# Sheet1.net
KiCad netlist of a schematic drawn in Altium Designer
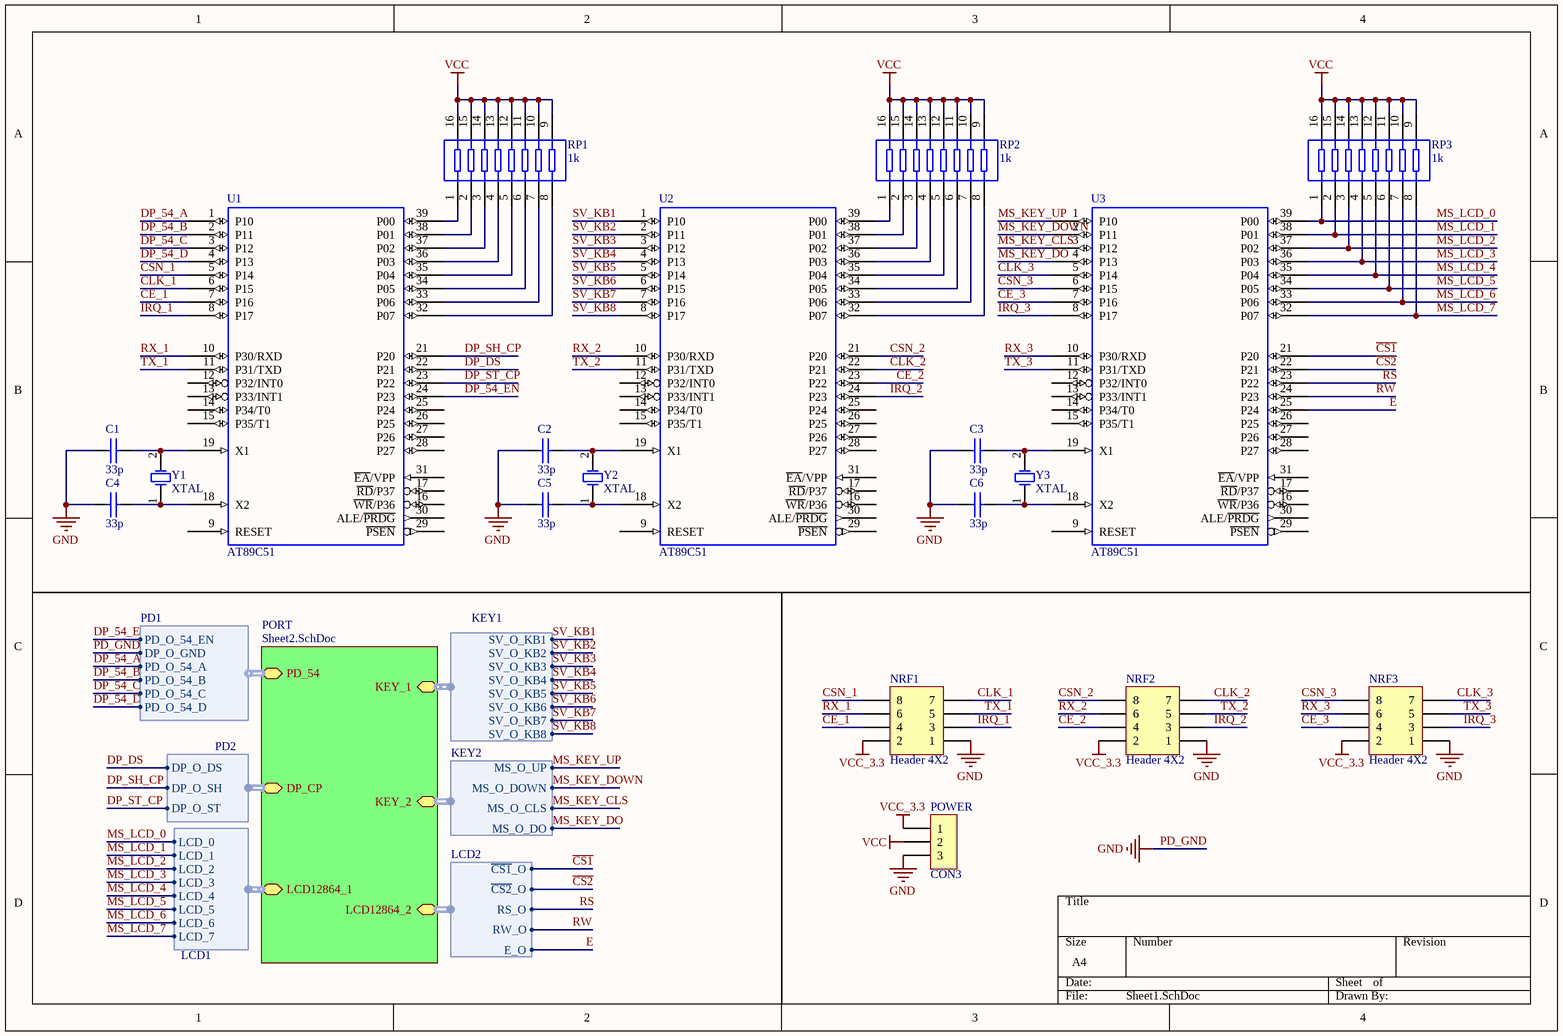
[diagram p0: Sheet1.SchDoc]

(export (version "E")
  (design (tool "Eeschema 10.0.6"))
  (components
    (comp (ref "C1")
      (value "33p")
      (footprint "RAD0.1")
      (description "Capacitor")
      (libsource (lib "电容") (part "普通电容"))
    )
    (comp (ref "C2")
      (value "33p")
      (footprint "RAD0.1")
      (description "Capacitor")
      (libsource (lib "电容") (part "普通电容"))
    )
    (comp (ref "C3")
      (value "33p")
      (footprint "RAD0.1")
      (description "Capacitor")
      (libsource (lib "电容") (part "普通电容"))
    )
    (comp (ref "C4")
      (value "33p")
      (footprint "RAD0.1")
      (description "Capacitor")
      (libsource (lib "电容") (part "普通电容"))
    )
    (comp (ref "C5")
      (value "33p")
      (footprint "RAD0.1")
      (description "Capacitor")
      (libsource (lib "电容") (part "普通电容"))
    )
    (comp (ref "C6")
      (value "33p")
      (footprint "RAD0.1")
      (description "Capacitor")
      (libsource (lib "电容") (part "普通电容"))
    )
    (comp (ref "NRF1")
      (value "Header 4X2")
      (footprint "HDR2X4")
      (description "Header, 4-Pin, Dual row")
      (fields (field (name "PUBLISHER") "Altium Limited"))
      (libsource (lib "Miscellaneous Connectors") (part "Header 4X2"))
    )
    (comp (ref "NRF2")
      (value "Header 4X2")
      (footprint "HDR2X4")
      (description "Header, 4-Pin, Dual row")
      (fields (field (name "PUBLISHER") "Altium Limited"))
      (libsource (lib "Miscellaneous Connectors") (part "Header 4X2"))
    )
    (comp (ref "NRF3")
      (value "Header 4X2")
      (footprint "HDR2X4")
      (description "Header, 4-Pin, Dual row")
      (fields (field (name "PUBLISHER") "Altium Limited"))
      (libsource (lib "Miscellaneous Connectors") (part "Header 4X2"))
    )
    (comp (ref "POWER") (value "CON3") (description "Connector") (libsource (lib "插件") (part "CON3")))
    (comp (ref "RP1") (value "1k") (footprint "DIP16") (libsource (lib "电阻") (part "RESPACK4")))
    (comp (ref "RP2") (value "1k") (footprint "DIP16") (libsource (lib "电阻") (part "RESPACK4")))
    (comp (ref "RP3") (value "1k") (footprint "DIP16") (libsource (lib "电阻") (part "RESPACK4")))
    (comp (ref "U1") (value "AT89C51") (footprint "DIP-40") (libsource (lib "单片机及相关") (part "AT89C51")))
    (comp (ref "U2") (value "AT89C51") (footprint "DIP-40") (libsource (lib "单片机及相关") (part "AT89C51")))
    (comp (ref "U3") (value "AT89C51") (footprint "DIP-40") (libsource (lib "单片机及相关") (part "AT89C51")))
    (comp (ref "Y1") (value "XTAL") (footprint "XTAL") (libsource (lib "我的元件库") (part "XTAL")))
    (comp (ref "Y2") (value "XTAL") (footprint "XTAL") (libsource (lib "我的元件库") (part "XTAL")))
    (comp (ref "Y3") (value "XTAL") (footprint "XTAL") (libsource (lib "我的元件库") (part "XTAL")))
  )
  (nets
    (net (code "7") (name "/CE_1") (class "Default")
      (node (ref "NRF1") (pin "4") (pinfunction "4_4") (pintype "passive"))
      (node (ref "U1") (pin "7") (pinfunction "P16_7") (pintype "bidirectional"))
    )
    (net (code "8") (name "/CE_2") (class "Default")
      (node (ref "NRF2") (pin "4") (pinfunction "4_4") (pintype "passive"))
      (node (ref "U2") (pin "23") (pinfunction "P22_23") (pintype "bidirectional"))
    )
    (net (code "9") (name "/CE_3") (class "Default")
      (node (ref "NRF3") (pin "4") (pinfunction "4_4") (pintype "passive"))
      (node (ref "U3") (pin "7") (pinfunction "P16_7") (pintype "bidirectional"))
    )
    (net (code "10") (name "/CLK_1") (class "Default")
      (node (ref "NRF1") (pin "7") (pinfunction "7_7") (pintype "passive"))
      (node (ref "U1") (pin "6") (pinfunction "P15_6") (pintype "bidirectional"))
    )
    (net (code "11") (name "/CLK_2") (class "Default")
      (node (ref "NRF2") (pin "7") (pinfunction "7_7") (pintype "passive"))
      (node (ref "U2") (pin "22") (pinfunction "P21_22") (pintype "bidirectional"))
    )
    (net (code "12") (name "/CLK_3") (class "Default")
      (node (ref "NRF3") (pin "7") (pinfunction "7_7") (pintype "passive"))
      (node (ref "U3") (pin "5") (pinfunction "P14_5") (pintype "bidirectional"))
    )
    (net (code "13") (name "/CSN_1") (class "Default")
      (node (ref "NRF1") (pin "8") (pinfunction "8_8") (pintype "passive"))
      (node (ref "U1") (pin "5") (pinfunction "P14_5") (pintype "bidirectional"))
    )
    (net (code "14") (name "/CSN_2") (class "Default")
      (node (ref "NRF2") (pin "8") (pinfunction "8_8") (pintype "passive"))
      (node (ref "U2") (pin "21") (pinfunction "P20_21") (pintype "bidirectional"))
    )
    (net (code "15") (name "/CSN_3") (class "Default")
      (node (ref "NRF3") (pin "8") (pinfunction "8_8") (pintype "passive"))
      (node (ref "U3") (pin "6") (pinfunction "P15_6") (pintype "bidirectional"))
    )
    (net (code "16") (name "/DP_54_A") (class "Default")
      (node (ref "U1") (pin "1") (pinfunction "P10_1") (pintype "bidirectional"))
    )
    (net (code "17") (name "/DP_54_B") (class "Default")
      (node (ref "U1") (pin "2") (pinfunction "P11_2") (pintype "bidirectional"))
    )
    (net (code "18") (name "/DP_54_C") (class "Default")
      (node (ref "U1") (pin "3") (pinfunction "P12_3") (pintype "bidirectional"))
    )
    (net (code "19") (name "/DP_54_D") (class "Default")
      (node (ref "U1") (pin "4") (pinfunction "P13_4") (pintype "bidirectional"))
    )
    (net (code "20") (name "/DP_54_EN") (class "Default")
      (node (ref "U1") (pin "24") (pinfunction "P23_24") (pintype "bidirectional"))
    )
    (net (code "21") (name "/DP_DS") (class "Default")
      (node (ref "U1") (pin "22") (pinfunction "P21_22") (pintype "bidirectional"))
    )
    (net (code "22") (name "/DP_SH_CP") (class "Default")
      (node (ref "U1") (pin "21") (pinfunction "P20_21") (pintype "bidirectional"))
    )
    (net (code "23") (name "/DP_ST_CP") (class "Default")
      (node (ref "U1") (pin "23") (pinfunction "P22_23") (pintype "bidirectional"))
    )
    (net (code "24") (name "/E") (class "Default")
      (node (ref "U3") (pin "25") (pinfunction "P24_25") (pintype "bidirectional"))
    )
    (net (code "25") (name "/IRQ_1") (class "Default")
      (node (ref "NRF1") (pin "3") (pinfunction "3_3") (pintype "passive"))
      (node (ref "U1") (pin "8") (pinfunction "P17_8") (pintype "bidirectional"))
    )
    (net (code "26") (name "/IRQ_2") (class "Default")
      (node (ref "NRF2") (pin "3") (pinfunction "3_3") (pintype "passive"))
      (node (ref "U2") (pin "24") (pinfunction "P23_24") (pintype "bidirectional"))
    )
    (net (code "27") (name "/IRQ_3") (class "Default")
      (node (ref "NRF3") (pin "3") (pinfunction "3_3") (pintype "passive"))
      (node (ref "U3") (pin "8") (pinfunction "P17_8") (pintype "bidirectional"))
    )
    (net (code "28") (name "/MS_KEY_CLS") (class "Default")
      (node (ref "U3") (pin "3") (pinfunction "P12_3") (pintype "bidirectional"))
    )
    (net (code "29") (name "/MS_KEY_DO") (class "Default")
      (node (ref "U3") (pin "4") (pinfunction "P13_4") (pintype "bidirectional"))
    )
    (net (code "30") (name "/MS_KEY_DOWN") (class "Default")
      (node (ref "U3") (pin "2") (pinfunction "P11_2") (pintype "bidirectional"))
    )
    (net (code "31") (name "/MS_KEY_UP") (class "Default")
      (node (ref "U3") (pin "1") (pinfunction "P10_1") (pintype "bidirectional"))
    )
    (net (code "32") (name "/MS_LCD_0") (class "Default")
      (node (ref "RP3") (pin "1") (pinfunction "1_1") (pintype "passive"))
      (node (ref "U3") (pin "39") (pinfunction "P00_39") (pintype "bidirectional"))
    )
    (net (code "33") (name "/MS_LCD_1") (class "Default")
      (node (ref "RP3") (pin "2") (pinfunction "2_2") (pintype "passive"))
      (node (ref "U3") (pin "38") (pinfunction "P01_38") (pintype "bidirectional"))
    )
    (net (code "34") (name "/MS_LCD_2") (class "Default")
      (node (ref "RP3") (pin "3") (pinfunction "3_3") (pintype "passive"))
      (node (ref "U3") (pin "37") (pinfunction "P02_37") (pintype "bidirectional"))
    )
    (net (code "35") (name "/MS_LCD_3") (class "Default")
      (node (ref "RP3") (pin "4") (pinfunction "4_4") (pintype "passive"))
      (node (ref "U3") (pin "36") (pinfunction "P03_36") (pintype "bidirectional"))
    )
    (net (code "36") (name "/MS_LCD_4") (class "Default")
      (node (ref "RP3") (pin "5") (pinfunction "5_5") (pintype "passive"))
      (node (ref "U3") (pin "35") (pinfunction "P04_35") (pintype "bidirectional"))
    )
    (net (code "37") (name "/MS_LCD_5") (class "Default")
      (node (ref "RP3") (pin "6") (pinfunction "6_6") (pintype "passive"))
      (node (ref "U3") (pin "34") (pinfunction "P05_34") (pintype "bidirectional"))
    )
    (net (code "38") (name "/MS_LCD_6") (class "Default")
      (node (ref "RP3") (pin "7") (pinfunction "7_7") (pintype "passive"))
      (node (ref "U3") (pin "33") (pinfunction "P06_33") (pintype "bidirectional"))
    )
    (net (code "39") (name "/MS_LCD_7") (class "Default")
      (node (ref "RP3") (pin "8") (pinfunction "8_8") (pintype "passive"))
      (node (ref "U3") (pin "32") (pinfunction "P07_32") (pintype "bidirectional"))
    )
    (net (code "40") (name "/RS") (class "Default")
      (node (ref "U3") (pin "23") (pinfunction "P22_23") (pintype "bidirectional"))
    )
    (net (code "41") (name "/RW") (class "Default")
      (node (ref "U3") (pin "24") (pinfunction "P23_24") (pintype "bidirectional"))
    )
    (net (code "42") (name "/RX_1") (class "Default")
      (node (ref "NRF1") (pin "6") (pinfunction "6_6") (pintype "passive"))
      (node (ref "U1") (pin "10") (pinfunction "P30/RXD_10") (pintype "bidirectional"))
    )
    (net (code "43") (name "/RX_2") (class "Default")
      (node (ref "NRF2") (pin "6") (pinfunction "6_6") (pintype "passive"))
      (node (ref "U2") (pin "10") (pinfunction "P30/RXD_10") (pintype "bidirectional"))
    )
    (net (code "44") (name "/RX_3") (class "Default")
      (node (ref "NRF3") (pin "6") (pinfunction "6_6") (pintype "passive"))
      (node (ref "U3") (pin "10") (pinfunction "P30/RXD_10") (pintype "bidirectional"))
    )
    (net (code "45") (name "/SV_KB1") (class "Default")
      (node (ref "U2") (pin "1") (pinfunction "P10_1") (pintype "bidirectional"))
    )
    (net (code "46") (name "/SV_KB2") (class "Default")
      (node (ref "U2") (pin "2") (pinfunction "P11_2") (pintype "bidirectional"))
    )
    (net (code "47") (name "/SV_KB3") (class "Default")
      (node (ref "U2") (pin "3") (pinfunction "P12_3") (pintype "bidirectional"))
    )
    (net (code "48") (name "/SV_KB4") (class "Default")
      (node (ref "U2") (pin "4") (pinfunction "P13_4") (pintype "bidirectional"))
    )
    (net (code "49") (name "/SV_KB5") (class "Default")
      (node (ref "U2") (pin "5") (pinfunction "P14_5") (pintype "bidirectional"))
    )
    (net (code "50") (name "/SV_KB6") (class "Default")
      (node (ref "U2") (pin "6") (pinfunction "P15_6") (pintype "bidirectional"))
    )
    (net (code "51") (name "/SV_KB7") (class "Default")
      (node (ref "U2") (pin "7") (pinfunction "P16_7") (pintype "bidirectional"))
    )
    (net (code "52") (name "/SV_KB8") (class "Default")
      (node (ref "U2") (pin "8") (pinfunction "P17_8") (pintype "bidirectional"))
    )
    (net (code "53") (name "/TX_1") (class "Default")
      (node (ref "NRF1") (pin "5") (pinfunction "5_5") (pintype "passive"))
      (node (ref "U1") (pin "11") (pinfunction "P31/TXD_11") (pintype "bidirectional"))
    )
    (net (code "54") (name "/TX_2") (class "Default")
      (node (ref "NRF2") (pin "5") (pinfunction "5_5") (pintype "passive"))
      (node (ref "U2") (pin "11") (pinfunction "P31/TXD_11") (pintype "bidirectional"))
    )
    (net (code "55") (name "/TX_3") (class "Default")
      (node (ref "NRF3") (pin "5") (pinfunction "5_5") (pintype "passive"))
      (node (ref "U3") (pin "11") (pinfunction "P31/TXD_11") (pintype "bidirectional"))
    )
    (net (code "62") (name "/~{CS1}") (class "Default")
      (node (ref "U3") (pin "21") (pinfunction "P20_21") (pintype "bidirectional"))
    )
    (net (code "63") (name "/~{CS2}") (class "Default")
      (node (ref "U3") (pin "22") (pinfunction "P21_22") (pintype "bidirectional"))
    )
    (net (code "64") (name "GND") (class "Default")
      (node (ref "C1") (pin "1") (pinfunction "1_1") (pintype "passive"))
      (node (ref "C2") (pin "1") (pinfunction "1_1") (pintype "passive"))
      (node (ref "C3") (pin "1") (pinfunction "1_1") (pintype "passive"))
      (node (ref "C4") (pin "1") (pinfunction "1_1") (pintype "passive"))
      (node (ref "C5") (pin "1") (pinfunction "1_1") (pintype "passive"))
      (node (ref "C6") (pin "1") (pinfunction "1_1") (pintype "passive"))
      (node (ref "NRF1") (pin "1") (pinfunction "1_1") (pintype "passive"))
      (node (ref "NRF2") (pin "1") (pinfunction "1_1") (pintype "passive"))
      (node (ref "NRF3") (pin "1") (pinfunction "1_1") (pintype "passive"))
      (node (ref "POWER") (pin "3") (pinfunction "3_3") (pintype "passive"))
      (node (ref "U1") (pin "20") (pinfunction "GND_20") (pintype "power_in"))
      (node (ref "U2") (pin "20") (pinfunction "GND_20") (pintype "power_in"))
      (node (ref "U3") (pin "20") (pinfunction "GND_20") (pintype "power_in"))
    )
    (net (code "65") (name "Net-(U1-P00)") (class "Default")
      (node (ref "RP1") (pin "1") (pinfunction "1_1") (pintype "passive"))
      (node (ref "U1") (pin "39") (pinfunction "P00_39") (pintype "bidirectional"))
    )
    (net (code "66") (name "Net-(U1-P01)") (class "Default")
      (node (ref "RP1") (pin "2") (pinfunction "2_2") (pintype "passive"))
      (node (ref "U1") (pin "38") (pinfunction "P01_38") (pintype "bidirectional"))
    )
    (net (code "67") (name "Net-(U1-P02)") (class "Default")
      (node (ref "RP1") (pin "3") (pinfunction "3_3") (pintype "passive"))
      (node (ref "U1") (pin "37") (pinfunction "P02_37") (pintype "bidirectional"))
    )
    (net (code "68") (name "Net-(U1-P03)") (class "Default")
      (node (ref "RP1") (pin "4") (pinfunction "4_4") (pintype "passive"))
      (node (ref "U1") (pin "36") (pinfunction "P03_36") (pintype "bidirectional"))
    )
    (net (code "69") (name "Net-(U1-P04)") (class "Default")
      (node (ref "RP1") (pin "5") (pinfunction "5_5") (pintype "passive"))
      (node (ref "U1") (pin "35") (pinfunction "P04_35") (pintype "bidirectional"))
    )
    (net (code "70") (name "Net-(U1-P05)") (class "Default")
      (node (ref "RP1") (pin "6") (pinfunction "6_6") (pintype "passive"))
      (node (ref "U1") (pin "34") (pinfunction "P05_34") (pintype "bidirectional"))
    )
    (net (code "71") (name "Net-(U1-P06)") (class "Default")
      (node (ref "RP1") (pin "7") (pinfunction "7_7") (pintype "passive"))
      (node (ref "U1") (pin "33") (pinfunction "P06_33") (pintype "bidirectional"))
    )
    (net (code "72") (name "Net-(U1-P07)") (class "Default")
      (node (ref "RP1") (pin "8") (pinfunction "8_8") (pintype "passive"))
      (node (ref "U1") (pin "32") (pinfunction "P07_32") (pintype "bidirectional"))
    )
    (net (code "73") (name "Net-(U1-X1)") (class "Default")
      (node (ref "C1") (pin "2") (pinfunction "2_2") (pintype "passive"))
      (node (ref "U1") (pin "19") (pinfunction "X1_19") (pintype "input"))
      (node (ref "Y1") (pin "2") (pinfunction "2_2") (pintype "passive"))
    )
    (net (code "74") (name "Net-(U1-X2)") (class "Default")
      (node (ref "C4") (pin "2") (pinfunction "2_2") (pintype "passive"))
      (node (ref "U1") (pin "18") (pinfunction "X2_18") (pintype "input"))
      (node (ref "Y1") (pin "1") (pinfunction "1_1") (pintype "passive"))
    )
    (net (code "75") (name "Net-(U2-P00)") (class "Default")
      (node (ref "RP2") (pin "1") (pinfunction "1_1") (pintype "passive"))
      (node (ref "U2") (pin "39") (pinfunction "P00_39") (pintype "bidirectional"))
    )
    (net (code "76") (name "Net-(U2-P01)") (class "Default")
      (node (ref "RP2") (pin "2") (pinfunction "2_2") (pintype "passive"))
      (node (ref "U2") (pin "38") (pinfunction "P01_38") (pintype "bidirectional"))
    )
    (net (code "77") (name "Net-(U2-P02)") (class "Default")
      (node (ref "RP2") (pin "3") (pinfunction "3_3") (pintype "passive"))
      (node (ref "U2") (pin "37") (pinfunction "P02_37") (pintype "bidirectional"))
    )
    (net (code "78") (name "Net-(U2-P03)") (class "Default")
      (node (ref "RP2") (pin "4") (pinfunction "4_4") (pintype "passive"))
      (node (ref "U2") (pin "36") (pinfunction "P03_36") (pintype "bidirectional"))
    )
    (net (code "79") (name "Net-(U2-P04)") (class "Default")
      (node (ref "RP2") (pin "5") (pinfunction "5_5") (pintype "passive"))
      (node (ref "U2") (pin "35") (pinfunction "P04_35") (pintype "bidirectional"))
    )
    (net (code "80") (name "Net-(U2-P05)") (class "Default")
      (node (ref "RP2") (pin "6") (pinfunction "6_6") (pintype "passive"))
      (node (ref "U2") (pin "34") (pinfunction "P05_34") (pintype "bidirectional"))
    )
    (net (code "81") (name "Net-(U2-P06)") (class "Default")
      (node (ref "RP2") (pin "7") (pinfunction "7_7") (pintype "passive"))
      (node (ref "U2") (pin "33") (pinfunction "P06_33") (pintype "bidirectional"))
    )
    (net (code "82") (name "Net-(U2-P07)") (class "Default")
      (node (ref "RP2") (pin "8") (pinfunction "8_8") (pintype "passive"))
      (node (ref "U2") (pin "32") (pinfunction "P07_32") (pintype "bidirectional"))
    )
    (net (code "83") (name "Net-(U2-X1)") (class "Default")
      (node (ref "C2") (pin "2") (pinfunction "2_2") (pintype "passive"))
      (node (ref "U2") (pin "19") (pinfunction "X1_19") (pintype "input"))
      (node (ref "Y2") (pin "2") (pinfunction "2_2") (pintype "passive"))
    )
    (net (code "84") (name "Net-(U2-X2)") (class "Default")
      (node (ref "C5") (pin "2") (pinfunction "2_2") (pintype "passive"))
      (node (ref "U2") (pin "18") (pinfunction "X2_18") (pintype "input"))
      (node (ref "Y2") (pin "1") (pinfunction "1_1") (pintype "passive"))
    )
    (net (code "85") (name "Net-(U3-X1)") (class "Default")
      (node (ref "C3") (pin "2") (pinfunction "2_2") (pintype "passive"))
      (node (ref "U3") (pin "19") (pinfunction "X1_19") (pintype "input"))
      (node (ref "Y3") (pin "2") (pinfunction "2_2") (pintype "passive"))
    )
    (net (code "86") (name "Net-(U3-X2)") (class "Default")
      (node (ref "C6") (pin "2") (pinfunction "2_2") (pintype "passive"))
      (node (ref "U3") (pin "18") (pinfunction "X2_18") (pintype "input"))
      (node (ref "Y3") (pin "1") (pinfunction "1_1") (pintype "passive"))
    )
    (net (code "87") (name "VCC") (class "Default")
      (node (ref "POWER") (pin "2") (pinfunction "2_2") (pintype "passive"))
      (node (ref "RP1") (pin "10") (pinfunction "10_10") (pintype "passive"))
      (node (ref "RP1") (pin "11") (pinfunction "11_11") (pintype "passive"))
      (node (ref "RP1") (pin "12") (pinfunction "12_12") (pintype "passive"))
      (node (ref "RP1") (pin "13") (pinfunction "13_13") (pintype "passive"))
      (node (ref "RP1") (pin "14") (pinfunction "14_14") (pintype "passive"))
      (node (ref "RP1") (pin "15") (pinfunction "15_15") (pintype "passive"))
      (node (ref "RP1") (pin "16") (pinfunction "16_16") (pintype "passive"))
      (node (ref "RP1") (pin "9") (pinfunction "9_9") (pintype "passive"))
      (node (ref "RP2") (pin "10") (pinfunction "10_10") (pintype "passive"))
      (node (ref "RP2") (pin "11") (pinfunction "11_11") (pintype "passive"))
      (node (ref "RP2") (pin "12") (pinfunction "12_12") (pintype "passive"))
      (node (ref "RP2") (pin "13") (pinfunction "13_13") (pintype "passive"))
      (node (ref "RP2") (pin "14") (pinfunction "14_14") (pintype "passive"))
      (node (ref "RP2") (pin "15") (pinfunction "15_15") (pintype "passive"))
      (node (ref "RP2") (pin "16") (pinfunction "16_16") (pintype "passive"))
      (node (ref "RP2") (pin "9") (pinfunction "9_9") (pintype "passive"))
      (node (ref "RP3") (pin "10") (pinfunction "10_10") (pintype "passive"))
      (node (ref "RP3") (pin "11") (pinfunction "11_11") (pintype "passive"))
      (node (ref "RP3") (pin "12") (pinfunction "12_12") (pintype "passive"))
      (node (ref "RP3") (pin "13") (pinfunction "13_13") (pintype "passive"))
      (node (ref "RP3") (pin "14") (pinfunction "14_14") (pintype "passive"))
      (node (ref "RP3") (pin "15") (pinfunction "15_15") (pintype "passive"))
      (node (ref "RP3") (pin "16") (pinfunction "16_16") (pintype "passive"))
      (node (ref "RP3") (pin "9") (pinfunction "9_9") (pintype "passive"))
      (node (ref "U1") (pin "40") (pinfunction "VCC_40") (pintype "power_in"))
      (node (ref "U2") (pin "40") (pinfunction "VCC_40") (pintype "power_in"))
      (node (ref "U3") (pin "40") (pinfunction "VCC_40") (pintype "power_in"))
    )
    (net (code "88") (name "VCC_3.3") (class "Default")
      (node (ref "NRF1") (pin "2") (pinfunction "2_2") (pintype "passive"))
      (node (ref "NRF2") (pin "2") (pinfunction "2_2") (pintype "passive"))
      (node (ref "NRF3") (pin "2") (pinfunction "2_2") (pintype "passive"))
      (node (ref "POWER") (pin "1") (pinfunction "1_1") (pintype "passive"))
    )
    (net (code "89") (name "unconnected-(U1-ALE{slash}~{PRDG}-Pad30)") (class "Default")
      (node (ref "U1") (pin "30") (pinfunction "ALE/~{PRDG}_30") (pintype "output"))
    )
    (net (code "90") (name "unconnected-(U1-P24-Pad25)") (class "Default")
      (node (ref "U1") (pin "25") (pinfunction "P24_25") (pintype "bidirectional"))
    )
    (net (code "91") (name "unconnected-(U1-P25-Pad26)") (class "Default")
      (node (ref "U1") (pin "26") (pinfunction "P25_26") (pintype "bidirectional"))
    )
    (net (code "92") (name "unconnected-(U1-P26-Pad27)") (class "Default")
      (node (ref "U1") (pin "27") (pinfunction "P26_27") (pintype "bidirectional"))
    )
    (net (code "93") (name "unconnected-(U1-P27-Pad28)") (class "Default")
      (node (ref "U1") (pin "28") (pinfunction "P27_28") (pintype "bidirectional"))
    )
    (net (code "94") (name "unconnected-(U1-P32{slash}INT0-Pad12)") (class "Default")
      (node (ref "U1") (pin "12") (pinfunction "P32/INT0_12") (pintype "bidirectional"))
    )
    (net (code "95") (name "unconnected-(U1-P33{slash}INT1-Pad13)") (class "Default")
      (node (ref "U1") (pin "13") (pinfunction "P33/INT1_13") (pintype "bidirectional"))
    )
    (net (code "96") (name "unconnected-(U1-P34{slash}T0-Pad14)") (class "Default")
      (node (ref "U1") (pin "14") (pinfunction "P34/T0_14") (pintype "bidirectional"))
    )
    (net (code "97") (name "unconnected-(U1-P35{slash}T1-Pad15)") (class "Default")
      (node (ref "U1") (pin "15") (pinfunction "P35/T1_15") (pintype "bidirectional"))
    )
    (net (code "98") (name "unconnected-(U1-RESET-Pad9)") (class "Default")
      (node (ref "U1") (pin "9") (pinfunction "RESET_9") (pintype "input"))
    )
    (net (code "99") (name "unconnected-(U1-~{EA}{slash}VPP-Pad31)") (class "Default")
      (node (ref "U1") (pin "31") (pinfunction "~{EA}/VPP_31") (pintype "input"))
    )
    (net (code "100") (name "unconnected-(U1-~{PSEN}-Pad29)") (class "Default")
      (node (ref "U1") (pin "29") (pinfunction "~{PSEN}_29") (pintype "output"))
    )
    (net (code "101") (name "unconnected-(U1-~{RD}{slash}P37-Pad17)") (class "Default")
      (node (ref "U1") (pin "17") (pinfunction "~{RD}/P37_17") (pintype "bidirectional"))
    )
    (net (code "102") (name "unconnected-(U1-~{WR}{slash}P36-Pad16)") (class "Default")
      (node (ref "U1") (pin "16") (pinfunction "~{WR}/P36_16") (pintype "bidirectional"))
    )
    (net (code "103") (name "unconnected-(U2-ALE{slash}~{PRDG}-Pad30)") (class "Default")
      (node (ref "U2") (pin "30") (pinfunction "ALE/~{PRDG}_30") (pintype "output"))
    )
    (net (code "104") (name "unconnected-(U2-P24-Pad25)") (class "Default")
      (node (ref "U2") (pin "25") (pinfunction "P24_25") (pintype "bidirectional"))
    )
    (net (code "105") (name "unconnected-(U2-P25-Pad26)") (class "Default")
      (node (ref "U2") (pin "26") (pinfunction "P25_26") (pintype "bidirectional"))
    )
    (net (code "106") (name "unconnected-(U2-P26-Pad27)") (class "Default")
      (node (ref "U2") (pin "27") (pinfunction "P26_27") (pintype "bidirectional"))
    )
    (net (code "107") (name "unconnected-(U2-P27-Pad28)") (class "Default")
      (node (ref "U2") (pin "28") (pinfunction "P27_28") (pintype "bidirectional"))
    )
    (net (code "108") (name "unconnected-(U2-P32{slash}INT0-Pad12)") (class "Default")
      (node (ref "U2") (pin "12") (pinfunction "P32/INT0_12") (pintype "bidirectional"))
    )
    (net (code "109") (name "unconnected-(U2-P33{slash}INT1-Pad13)") (class "Default")
      (node (ref "U2") (pin "13") (pinfunction "P33/INT1_13") (pintype "bidirectional"))
    )
    (net (code "110") (name "unconnected-(U2-P34{slash}T0-Pad14)") (class "Default")
      (node (ref "U2") (pin "14") (pinfunction "P34/T0_14") (pintype "bidirectional"))
    )
    (net (code "111") (name "unconnected-(U2-P35{slash}T1-Pad15)") (class "Default")
      (node (ref "U2") (pin "15") (pinfunction "P35/T1_15") (pintype "bidirectional"))
    )
    (net (code "112") (name "unconnected-(U2-RESET-Pad9)") (class "Default")
      (node (ref "U2") (pin "9") (pinfunction "RESET_9") (pintype "input"))
    )
    (net (code "113") (name "unconnected-(U2-~{EA}{slash}VPP-Pad31)") (class "Default")
      (node (ref "U2") (pin "31") (pinfunction "~{EA}/VPP_31") (pintype "input"))
    )
    (net (code "114") (name "unconnected-(U2-~{PSEN}-Pad29)") (class "Default")
      (node (ref "U2") (pin "29") (pinfunction "~{PSEN}_29") (pintype "output"))
    )
    (net (code "115") (name "unconnected-(U2-~{RD}{slash}P37-Pad17)") (class "Default")
      (node (ref "U2") (pin "17") (pinfunction "~{RD}/P37_17") (pintype "bidirectional"))
    )
    (net (code "116") (name "unconnected-(U2-~{WR}{slash}P36-Pad16)") (class "Default")
      (node (ref "U2") (pin "16") (pinfunction "~{WR}/P36_16") (pintype "bidirectional"))
    )
    (net (code "117") (name "unconnected-(U3-ALE{slash}~{PRDG}-Pad30)") (class "Default")
      (node (ref "U3") (pin "30") (pinfunction "ALE/~{PRDG}_30") (pintype "output"))
    )
    (net (code "118") (name "unconnected-(U3-P25-Pad26)") (class "Default")
      (node (ref "U3") (pin "26") (pinfunction "P25_26") (pintype "bidirectional"))
    )
    (net (code "119") (name "unconnected-(U3-P26-Pad27)") (class "Default")
      (node (ref "U3") (pin "27") (pinfunction "P26_27") (pintype "bidirectional"))
    )
    (net (code "120") (name "unconnected-(U3-P27-Pad28)") (class "Default")
      (node (ref "U3") (pin "28") (pinfunction "P27_28") (pintype "bidirectional"))
    )
    (net (code "121") (name "unconnected-(U3-P32{slash}INT0-Pad12)") (class "Default")
      (node (ref "U3") (pin "12") (pinfunction "P32/INT0_12") (pintype "bidirectional"))
    )
    (net (code "122") (name "unconnected-(U3-P33{slash}INT1-Pad13)") (class "Default")
      (node (ref "U3") (pin "13") (pinfunction "P33/INT1_13") (pintype "bidirectional"))
    )
    (net (code "123") (name "unconnected-(U3-P34{slash}T0-Pad14)") (class "Default")
      (node (ref "U3") (pin "14") (pinfunction "P34/T0_14") (pintype "bidirectional"))
    )
    (net (code "124") (name "unconnected-(U3-P35{slash}T1-Pad15)") (class "Default")
      (node (ref "U3") (pin "15") (pinfunction "P35/T1_15") (pintype "bidirectional"))
    )
    (net (code "125") (name "unconnected-(U3-RESET-Pad9)") (class "Default")
      (node (ref "U3") (pin "9") (pinfunction "RESET_9") (pintype "input"))
    )
    (net (code "126") (name "unconnected-(U3-~{EA}{slash}VPP-Pad31)") (class "Default")
      (node (ref "U3") (pin "31") (pinfunction "~{EA}/VPP_31") (pintype "input"))
    )
    (net (code "127") (name "unconnected-(U3-~{PSEN}-Pad29)") (class "Default")
      (node (ref "U3") (pin "29") (pinfunction "~{PSEN}_29") (pintype "output"))
    )
    (net (code "128") (name "unconnected-(U3-~{RD}{slash}P37-Pad17)") (class "Default")
      (node (ref "U3") (pin "17") (pinfunction "~{RD}/P37_17") (pintype "bidirectional"))
    )
    (net (code "129") (name "unconnected-(U3-~{WR}{slash}P36-Pad16)") (class "Default")
      (node (ref "U3") (pin "16") (pinfunction "~{WR}/P36_16") (pintype "bidirectional"))
    )
  )
)
